# Connectors.net
KiCad netlist of a schematic drawn in Altium Designer
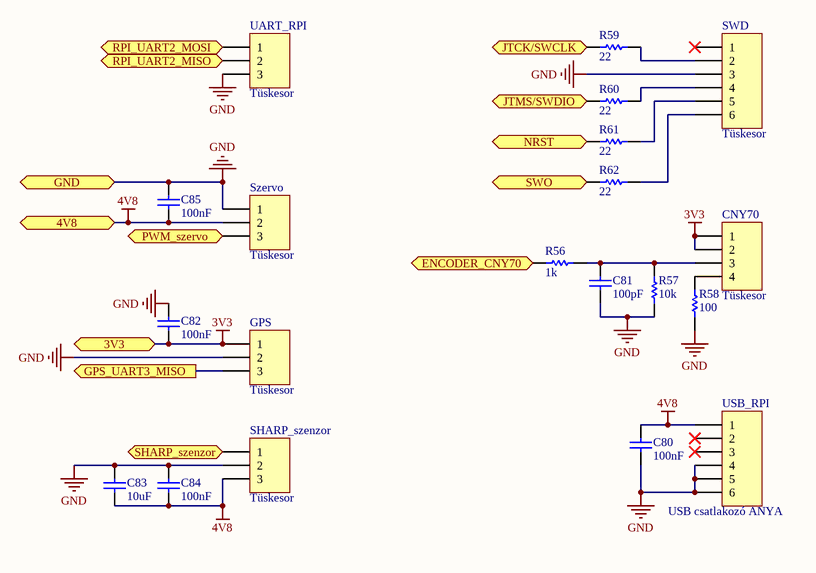
[diagram p0: Connectors.SchDoc]

(export (version "E")
  (design (tool "Eeschema 10.0.6"))
  (components
    (comp (ref "C80")
      (value "100nF")
      (footprint "FP_0603_CAP_080")
      (description "Capacitor")
      (fields (field (name "Comment") "Cap") (field (name "PUBLISHER") "Altium Limited"))
      (libsource (lib "Miscellaneous Devices") (part "Cap"))
    )
    (comp (ref "C81")
      (value "100pF")
      (footprint "FP_0603_CAP_080")
      (description "Capacitor")
      (fields (field (name "Comment") "Cap") (field (name "PUBLISHER") "Altium Limited"))
      (libsource (lib "Miscellaneous Devices") (part "Cap"))
    )
    (comp (ref "C82")
      (value "100nF")
      (footprint "FP_0603_CAP_080")
      (description "Capacitor")
      (fields (field (name "Comment") "Cap") (field (name "PUBLISHER") "Altium Limited"))
      (libsource (lib "Miscellaneous Devices") (part "Cap"))
    )
    (comp (ref "C83")
      (value "10uF")
      (footprint "FP_1206_CAP_125")
      (description "Capacitor")
      (fields (field (name "Comment") "Cap") (field (name "PUBLISHER") "Altium Limited"))
      (libsource (lib "Miscellaneous Devices") (part "Cap"))
    )
    (comp (ref "C84")
      (value "100nF")
      (footprint "FP_0603_CAP_080")
      (description "Capacitor")
      (fields (field (name "Comment") "Cap") (field (name "PUBLISHER") "Altium Limited"))
      (libsource (lib "Miscellaneous Devices") (part "Cap"))
    )
    (comp (ref "C85")
      (value "100nF")
      (footprint "FP_0603_CAP_080")
      (description "Capacitor")
      (fields (field (name "Comment") "Cap") (field (name "PUBLISHER") "Altium Limited"))
      (libsource (lib "Miscellaneous Devices") (part "Cap"))
    )
    (comp (ref "CNY70")
      (value "Tüskesor")
      (footprint "FP_CONN4_TUSKE_254MM")
      (description "Header, 4-Pin")
      (fields (field (name "PUBLISHER") "Altium Limited"))
      (libsource (lib "Miscellaneous Connectors") (part "Header 4"))
    )
    (comp (ref "GPS")
      (value "Tüskesor")
      (footprint "FP_CONN3_TUSKE_254MM")
      (description "Header, 3-Pin")
      (fields (field (name "PUBLISHER") "Altium Limited"))
      (libsource (lib "Miscellaneous Connectors") (part "Header 3"))
    )
    (comp (ref "R56")
      (value "1k")
      (footprint "FP_0603_RES")
      (description "Resistor")
      (fields (field (name "Comment") "Res1") (field (name "PUBLISHER") "Altium Limited"))
      (libsource (lib "Miscellaneous Devices") (part "Res1"))
    )
    (comp (ref "R57")
      (value "10k")
      (footprint "FP_0603_RES")
      (description "Resistor")
      (fields (field (name "Comment") "Res1") (field (name "PUBLISHER") "Altium Limited"))
      (libsource (lib "Miscellaneous Devices") (part "Res1"))
    )
    (comp (ref "R58")
      (value "100")
      (footprint "FP_0603_RES")
      (description "Resistor")
      (fields (field (name "Comment") "Res1") (field (name "PUBLISHER") "Altium Limited"))
      (libsource (lib "Miscellaneous Devices") (part "Res1"))
    )
    (comp (ref "R59")
      (value "22")
      (footprint "FP_0603_RES")
      (description "Resistor")
      (fields (field (name "Comment") "Res1") (field (name "PUBLISHER") "Altium Limited"))
      (libsource (lib "Miscellaneous Devices") (part "Res1"))
    )
    (comp (ref "R60")
      (value "22")
      (footprint "FP_0603_RES")
      (description "Resistor")
      (fields (field (name "Comment") "Res1") (field (name "PUBLISHER") "Altium Limited"))
      (libsource (lib "Miscellaneous Devices") (part "Res1"))
    )
    (comp (ref "R61")
      (value "22")
      (footprint "FP_0603_RES")
      (description "Resistor")
      (fields (field (name "Comment") "Res1") (field (name "PUBLISHER") "Altium Limited"))
      (libsource (lib "Miscellaneous Devices") (part "Res1"))
    )
    (comp (ref "R62")
      (value "22")
      (footprint "FP_0603_RES")
      (description "Resistor")
      (fields (field (name "Comment") "Res1") (field (name "PUBLISHER") "Altium Limited"))
      (libsource (lib "Miscellaneous Devices") (part "Res1"))
    )
    (comp (ref "SHARP_szenzor")
      (value "Tüskesor")
      (footprint "HDR1X3")
      (description "Header, 3-Pin")
      (fields (field (name "PUBLISHER") "Altium Limited"))
      (libsource (lib "Miscellaneous Connectors") (part "Header 3"))
    )
    (comp (ref "SWD")
      (value "Tüskesor")
      (footprint "HDR1X6")
      (description "Header, 6-Pin")
      (fields (field (name "PUBLISHER") "Altium Limited"))
      (libsource (lib "Miscellaneous Connectors") (part "Header 6"))
    )
    (comp (ref "Szervo")
      (value "Tüskesor")
      (footprint "FP_CONN3_TUSKE_254MM")
      (description "Header, 3-Pin")
      (fields (field (name "PUBLISHER") "Altium Limited"))
      (libsource (lib "Miscellaneous Connectors") (part "Header 3"))
    )
    (comp (ref "UART_RPI")
      (value "Tüskesor")
      (footprint "FP_CONN3_TUSKE_254MM")
      (description "Header, 3-Pin")
      (fields (field (name "PUBLISHER") "Altium Limited"))
      (libsource (lib "Miscellaneous Connectors") (part "Header 3"))
    )
    (comp (ref "USB_RPI")
      (value "USB csatlakozó ANYA")
      (footprint "USB_vertical")
      (description "Header, 6-Pin")
      (fields (field (name "PUBLISHER") "Altium Limited"))
      (libsource (lib "Miscellaneous Connectors") (part "Header 6"))
    )
  )
  (nets
    (net (code "1") (name "/ENCODER_CNY70") (class "Default")
      (node (ref "R56") (pin "2") (pinfunction "2_2") (pintype "passive"))
    )
    (net (code "2") (name "/GPS_UART3_MISO") (class "Default")
      (node (ref "GPS") (pin "3") (pinfunction "3_3") (pintype "passive"))
    )
    (net (code "3") (name "/JTCK{slash}SWCLK") (class "Default")
      (node (ref "R59") (pin "2") (pinfunction "2_2") (pintype "passive"))
    )
    (net (code "4") (name "/JTMS{slash}SWDIO") (class "Default")
      (node (ref "R60") (pin "2") (pinfunction "2_2") (pintype "passive"))
    )
    (net (code "5") (name "/NRST") (class "Default")
      (node (ref "R61") (pin "2") (pinfunction "2_2") (pintype "passive"))
    )
    (net (code "6") (name "/PWM_szervo") (class "Default")
      (node (ref "Szervo") (pin "3") (pinfunction "3_3") (pintype "passive"))
    )
    (net (code "7") (name "/RPI_UART2_MISO") (class "Default")
      (node (ref "UART_RPI") (pin "2") (pinfunction "2_2") (pintype "passive"))
    )
    (net (code "8") (name "/RPI_UART2_MOSI") (class "Default")
      (node (ref "UART_RPI") (pin "1") (pinfunction "1_1") (pintype "passive"))
    )
    (net (code "9") (name "/SHARP_szenzor") (class "Default")
      (node (ref "SHARP_szenzor") (pin "1") (pinfunction "1_1") (pintype "passive"))
    )
    (net (code "10") (name "/SWO") (class "Default")
      (node (ref "R62") (pin "2") (pinfunction "2_2") (pintype "passive"))
    )
    (net (code "11") (name "3V3") (class "Default")
      (node (ref "C82") (pin "1") (pinfunction "1_1") (pintype "passive"))
      (node (ref "CNY70") (pin "1") (pinfunction "1_1") (pintype "passive"))
      (node (ref "CNY70") (pin "2") (pinfunction "2_2") (pintype "passive"))
      (node (ref "GPS") (pin "1") (pinfunction "1_1") (pintype "passive"))
    )
    (net (code "12") (name "4V8") (class "Default")
      (node (ref "C80") (pin "2") (pinfunction "2_2") (pintype "passive"))
      (node (ref "C83") (pin "2") (pinfunction "2_2") (pintype "passive"))
      (node (ref "C84") (pin "1") (pinfunction "1_1") (pintype "passive"))
      (node (ref "C85") (pin "1") (pinfunction "1_1") (pintype "passive"))
      (node (ref "SHARP_szenzor") (pin "3") (pinfunction "3_3") (pintype "passive"))
      (node (ref "Szervo") (pin "2") (pinfunction "2_2") (pintype "passive"))
      (node (ref "USB_RPI") (pin "1") (pinfunction "1_1") (pintype "passive"))
    )
    (net (code "13") (name "GND") (class "Default")
      (node (ref "C80") (pin "1") (pinfunction "1_1") (pintype "passive"))
      (node (ref "C81") (pin "1") (pinfunction "1_1") (pintype "passive"))
      (node (ref "C82") (pin "2") (pinfunction "2_2") (pintype "passive"))
      (node (ref "C83") (pin "1") (pinfunction "1_1") (pintype "passive"))
      (node (ref "C84") (pin "2") (pinfunction "2_2") (pintype "passive"))
      (node (ref "C85") (pin "2") (pinfunction "2_2") (pintype "passive"))
      (node (ref "GPS") (pin "2") (pinfunction "2_2") (pintype "passive"))
      (node (ref "R57") (pin "1") (pinfunction "1_1") (pintype "passive"))
      (node (ref "R58") (pin "1") (pinfunction "1_1") (pintype "passive"))
      (node (ref "SHARP_szenzor") (pin "2") (pinfunction "2_2") (pintype "passive"))
      (node (ref "SWD") (pin "3") (pinfunction "3_3") (pintype "passive"))
      (node (ref "Szervo") (pin "1") (pinfunction "1_1") (pintype "passive"))
      (node (ref "UART_RPI") (pin "3") (pinfunction "3_3") (pintype "passive"))
      (node (ref "USB_RPI") (pin "4") (pinfunction "4_4") (pintype "passive"))
      (node (ref "USB_RPI") (pin "5") (pinfunction "5_5") (pintype "passive"))
      (node (ref "USB_RPI") (pin "6") (pinfunction "6_6") (pintype "passive"))
    )
    (net (code "14") (name "Net-(C81-Pad2)") (class "Default")
      (node (ref "C81") (pin "2") (pinfunction "2_2") (pintype "passive"))
      (node (ref "CNY70") (pin "3") (pinfunction "3_3") (pintype "passive"))
      (node (ref "R56") (pin "1") (pinfunction "1_1") (pintype "passive"))
      (node (ref "R57") (pin "2") (pinfunction "2_2") (pintype "passive"))
    )
    (net (code "15") (name "Net-(CNY70-Pad4)") (class "Default")
      (node (ref "CNY70") (pin "4") (pinfunction "4_4") (pintype "passive"))
      (node (ref "R58") (pin "2") (pinfunction "2_2") (pintype "passive"))
    )
    (net (code "16") (name "Net-(R59-Pad1)") (class "Default")
      (node (ref "R59") (pin "1") (pinfunction "1_1") (pintype "passive"))
      (node (ref "SWD") (pin "2") (pinfunction "2_2") (pintype "passive"))
    )
    (net (code "17") (name "Net-(R60-Pad1)") (class "Default")
      (node (ref "R60") (pin "1") (pinfunction "1_1") (pintype "passive"))
      (node (ref "SWD") (pin "4") (pinfunction "4_4") (pintype "passive"))
    )
    (net (code "18") (name "Net-(R61-Pad1)") (class "Default")
      (node (ref "R61") (pin "1") (pinfunction "1_1") (pintype "passive"))
      (node (ref "SWD") (pin "5") (pinfunction "5_5") (pintype "passive"))
    )
    (net (code "19") (name "Net-(R62-Pad1)") (class "Default")
      (node (ref "R62") (pin "1") (pinfunction "1_1") (pintype "passive"))
      (node (ref "SWD") (pin "6") (pinfunction "6_6") (pintype "passive"))
    )
    (net (code "20") (name "unconnected-(SWD-Pad1)") (class "Default")
      (node (ref "SWD") (pin "1") (pinfunction "1_1") (pintype "passive+no_connect"))
    )
    (net (code "21") (name "unconnected-(USB_RPI-Pad2)") (class "Default")
      (node (ref "USB_RPI") (pin "2") (pinfunction "2_2") (pintype "passive+no_connect"))
    )
    (net (code "22") (name "unconnected-(USB_RPI-Pad3)") (class "Default")
      (node (ref "USB_RPI") (pin "3") (pinfunction "3_3") (pintype "passive+no_connect"))
    )
  )
)
